# Power.net
KiCad netlist of a schematic drawn in Altium Designer
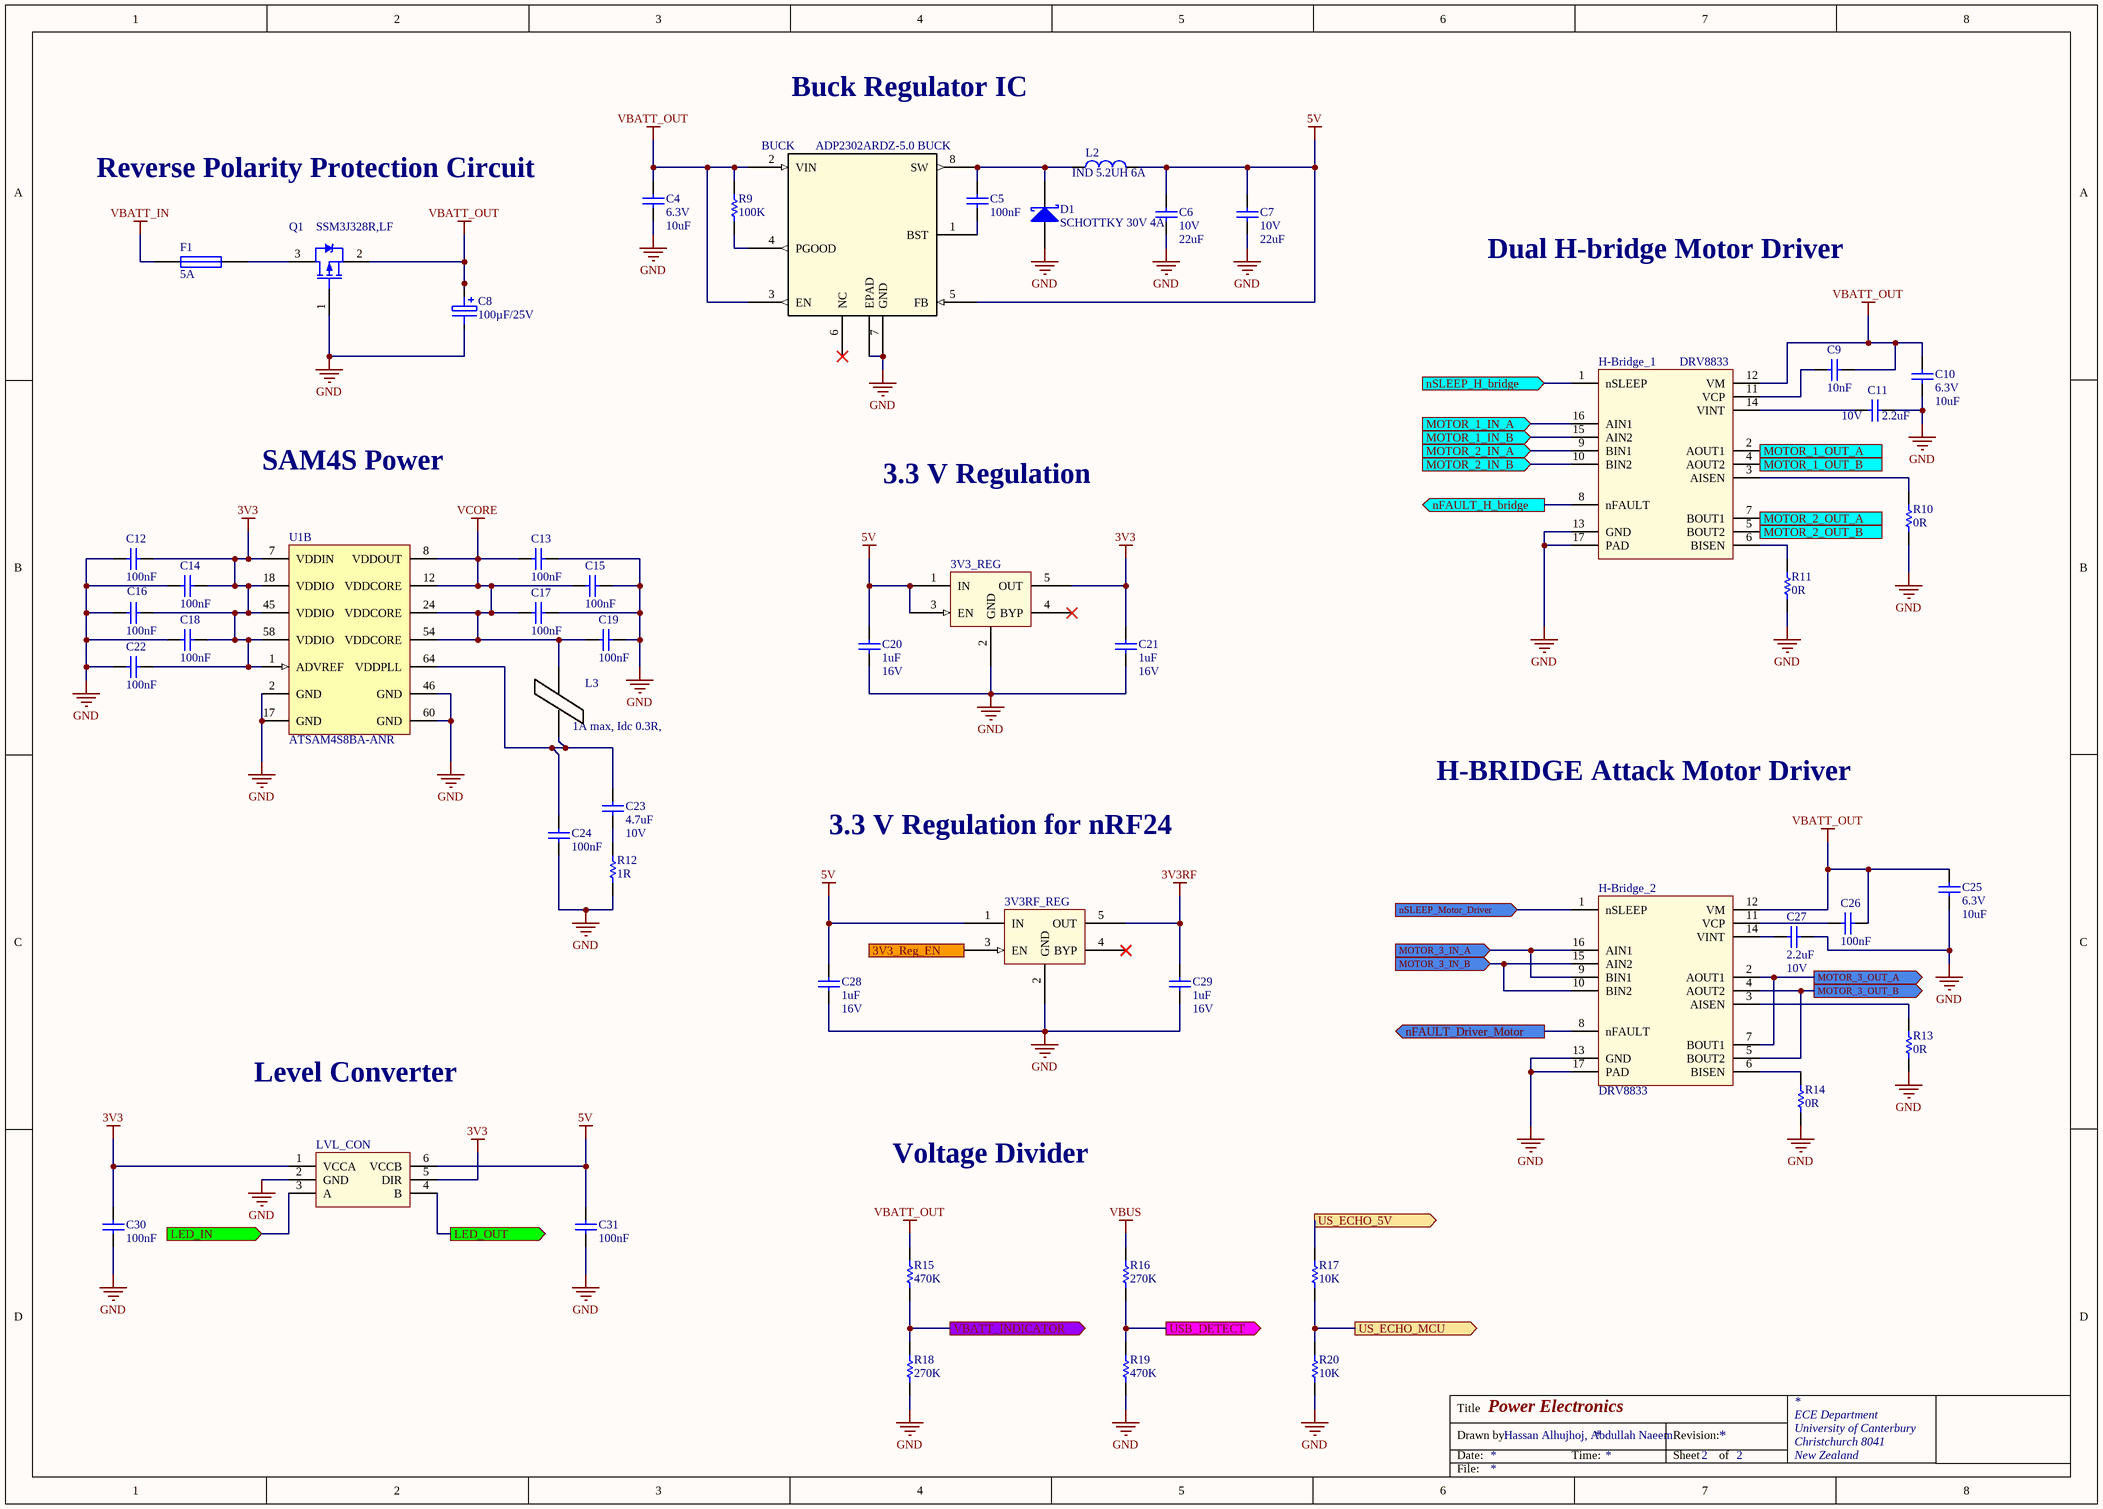
[diagram p0: Power.SchDoc]

(export (version "E")
  (design (tool "Eeschema 10.0.6"))
  (components
    (comp (ref "3V3RF_REG")
      (value "CAT6219-330TDGT3")
      (footprint "SOT95P280X145-5N")
      (description "IC REG LIN 3.3V 500MA TSOT23-5")
      (fields (field (name "BASE PART NUMBER") "CAT6219"))
      (libsource (lib "ENCE461AD19_19V2") (part "SV_CAT6219-330TDGT3"))
    )
    (comp (ref "3V3_REG")
      (value "CAT6219-330TDGT3")
      (footprint "SOT95P280X145-5N")
      (description "IC REG LIN 3.3V 500MA TSOT23-5")
      (fields (field (name "BASE PART NUMBER") "CAT6219"))
      (libsource (lib "ENCE461AD19_19V2") (part "SV_CAT6219-330TDGT3"))
    )
    (comp (ref "BUCK")
      (value "ADP2302ARDZ-5.0 BUCK")
      (footprint "RD_8_1")
      (description "IC REG BUCK 5V 2A 8SOIC")
      (fields (field (name "MANUFACTURER_PART_NUMBER") "ADP2302ARDZ-5.0-R7"))
      (libsource (lib "ENCE461AD19_19V2") (part "ADP2302ARDZ-5.0-R7"))
    )
    (comp (ref "C4")
      (value "10uF")
      (footprint "CAPC1608L")
      (description "CAP CER 10UF X5R +-20% 6V3 0603")
      (fields (field (name "VOLTAGE - RATED") "6.3V"))
      (libsource (lib "ECE AD19Components_19V1") (part "CC_10uF_0603"))
    )
    (comp (ref "C5")
      (value "100nF")
      (footprint "CAPC1608L")
      (description "CAP CER 100nF X7R +-10% 50V 0603")
      (libsource (lib "ECE AD19Components_19V1") (part "CC_100nF_0603"))
    )
    (comp (ref "C6")
      (value "22uF")
      (footprint "CAPC3216L")
      (description "CAP CER 22uF Y5V -20% +80% 10V 1206")
      (fields (field (name "MAX VOLTAGE") "10V"))
      (libsource (lib "ECE AD19Components_19V1") (part "CC_22uF_1206"))
    )
    (comp (ref "C7")
      (value "22uF")
      (footprint "CAPC3216L")
      (description "CAP CER 22uF Y5V -20% +80% 10V 1206")
      (fields (field (name "MAX VOLTAGE") "10V"))
      (libsource (lib "ECE AD19Components_19V1") (part "CC_22uF_1206"))
    )
    (comp (ref "C8")
      (value "100µF/25V")
      (footprint "CAPAE6666X77M")
      (description "CAP ALUM 100UF 25V 20% SMD")
      (fields
        (field (name "MANUFACTURER") "Nichicon")
        (field (name "MANUFACTURER PART NUMBER") "UWT1E101MCL1GS")
        (field (name "CAPACITANCE") "100µF/25V")
      )
      (libsource (lib "ECE AD19Components_19V1") (part "CA_100uF_25V"))
    )
    (comp (ref "C9")
      (value "10nF")
      (footprint "CAPC1608L")
      (description "CAP CER 10nF X7R +-10% 50V 0603")
      (libsource (lib "ECE AD19Components_19V1") (part "CC_10nF_0603"))
    )
    (comp (ref "C10")
      (value "10uF")
      (footprint "CAPC1608L")
      (description "CAP CER 10UF X5R +-20% 6V3 0603")
      (fields (field (name "VOLTAGE - RATED") "6.3V"))
      (libsource (lib "ECE AD19Components_19V1") (part "CC_10uF_0603"))
    )
    (comp (ref "C11")
      (value "2.2uF")
      (footprint "CAPC1608L")
      (description "CAP CER 2.2uF X5R +-20% 10V 0603")
      (fields (field (name "MAX VOLTAGE") "10V"))
      (libsource (lib "ECE AD19Components_19V1") (part "CC_2.2uF_0603"))
    )
    (comp (ref "C12")
      (value "100nF")
      (footprint "CAPC1608L")
      (description "CAP CER 100nF X7R +-10% 50V 0603")
      (libsource (lib "ECE AD19Components_19V1") (part "CC_100nF_0603"))
    )
    (comp (ref "C13")
      (value "100nF")
      (footprint "CAPC1608L")
      (description "CAP CER 100nF X7R +-10% 50V 0603")
      (libsource (lib "ECE AD19Components_19V1") (part "CC_100nF_0603"))
    )
    (comp (ref "C14")
      (value "100nF")
      (footprint "CAPC1608L")
      (description "CAP CER 100nF X7R +-10% 50V 0603")
      (libsource (lib "ECE AD19Components_19V1") (part "CC_100nF_0603"))
    )
    (comp (ref "C15")
      (value "100nF")
      (footprint "CAPC1608L")
      (description "CAP CER 100nF X7R +-10% 50V 0603")
      (libsource (lib "ECE AD19Components_19V1") (part "CC_100nF_0603"))
    )
    (comp (ref "C16")
      (value "100nF")
      (footprint "CAPC1608L")
      (description "CAP CER 100nF X7R +-10% 50V 0603")
      (libsource (lib "ECE AD19Components_19V1") (part "CC_100nF_0603"))
    )
    (comp (ref "C17")
      (value "100nF")
      (footprint "CAPC1608L")
      (description "CAP CER 100nF X7R +-10% 50V 0603")
      (libsource (lib "ECE AD19Components_19V1") (part "CC_100nF_0603"))
    )
    (comp (ref "C18")
      (value "100nF")
      (footprint "CAPC1608L")
      (description "CAP CER 100nF X7R +-10% 50V 0603")
      (libsource (lib "ECE AD19Components_19V1") (part "CC_100nF_0603"))
    )
    (comp (ref "C19")
      (value "100nF")
      (footprint "CAPC1608L")
      (description "CAP CER 100nF X7R +-10% 50V 0603")
      (libsource (lib "ECE AD19Components_19V1") (part "CC_100nF_0603"))
    )
    (comp (ref "C20")
      (value "1uF")
      (footprint "CAPC1608L")
      (description "CAP CER 1uF Y5V -20% +80% 16V 0603")
      (fields (field (name "MAX VOLTAGE") "16V"))
      (libsource (lib "ECE AD19Components_19V1") (part "CC_1uF_0603"))
    )
    (comp (ref "C21")
      (value "1uF")
      (footprint "CAPC1608L")
      (description "CAP CER 1uF Y5V -20% +80% 16V 0603")
      (fields (field (name "MAX VOLTAGE") "16V"))
      (libsource (lib "ECE AD19Components_19V1") (part "CC_1uF_0603"))
    )
    (comp (ref "C22")
      (value "100nF")
      (footprint "CAPC1608L")
      (description "CAP CER 100nF X7R +-10% 50V 0603")
      (libsource (lib "ECE AD19Components_19V1") (part "CC_100nF_0603"))
    )
    (comp (ref "C23")
      (value "4.7uF")
      (footprint "CAPC1608N")
      (description "CAP CER 4.7uF X5R +-20%  10V 0603")
      (fields (field (name "MAX VOLTAGE") "10V"))
      (libsource (lib "ECE AD19Components_19V1") (part "CC_4.7uF_0603"))
    )
    (comp (ref "C24")
      (value "100nF")
      (footprint "CAPC1608L")
      (description "CAP CER 100nF X7R +-10% 50V 0603")
      (libsource (lib "ECE AD19Components_19V1") (part "CC_100nF_0603"))
    )
    (comp (ref "C25")
      (value "10uF")
      (footprint "CAPC1608L")
      (description "CAP CER 10UF X5R +-20% 6V3 0603")
      (fields (field (name "VOLTAGE - RATED") "6.3V"))
      (libsource (lib "ECE AD19Components_19V1") (part "CC_10uF_0603"))
    )
    (comp (ref "C26")
      (value "100nF")
      (footprint "CAPC1608L")
      (description "CAP CER 100nF X7R +-10% 50V 0603")
      (libsource (lib "ECE AD19Components_19V1") (part "CC_100nF_0603"))
    )
    (comp (ref "C27")
      (value "2.2uF")
      (footprint "CAPC1608L")
      (description "CAP CER 2.2uF X5R +-20% 10V 0603")
      (fields (field (name "MAX VOLTAGE") "10V"))
      (libsource (lib "ECE AD19Components_19V1") (part "CC_2.2uF_0603"))
    )
    (comp (ref "C28")
      (value "1uF")
      (footprint "CAPC1608L")
      (description "CAP CER 1uF Y5V -20% +80% 16V 0603")
      (fields (field (name "MAX VOLTAGE") "16V"))
      (libsource (lib "ECE AD19Components_19V1") (part "CC_1uF_0603"))
    )
    (comp (ref "C29")
      (value "1uF")
      (footprint "CAPC1608L")
      (description "CAP CER 1uF Y5V -20% +80% 16V 0603")
      (fields (field (name "MAX VOLTAGE") "16V"))
      (libsource (lib "ECE AD19Components_19V1") (part "CC_1uF_0603"))
    )
    (comp (ref "C30")
      (value "100nF")
      (footprint "CAPC1608L")
      (description "CAP CER 100nF X7R +-10% 50V 0603")
      (libsource (lib "ECE AD19Components_19V1") (part "CC_100nF_0603"))
    )
    (comp (ref "C31")
      (value "100nF")
      (footprint "CAPC1608L")
      (description "CAP CER 100nF X7R +-10% 50V 0603")
      (libsource (lib "ECE AD19Components_19V1") (part "CC_100nF_0603"))
    )
    (comp (ref "D1")
      (value "SCHOTTKY 30V 4A")
      (footprint "SMC")
      (description "DIODE SCHOTTKY 30V 4A SMC")
      (fields
        (field (name "MANUFACTURER") "ON Semiconductor")
        (field (name "MANUFACTURER PART NUMBER") "MBRS330T3G")
      )
      (libsource (lib "ENCE461AD19_19V2") (part "MBRS330T3G"))
    )
    (comp (ref "F1")
      (value "5A")
      (footprint "RESC3216N")
      (description "Fuse 5.0A Fast Acting 1206 SMD")
      (fields (field (name "MANUFACTURER PART NUMBER") "C1F5") (field (name "MANUFACTURER") "Bel TRP"))
      (libsource (lib "ECE AD19Components_19V1") (part "FS_Fuse_5.0A"))
    )
    (comp (ref "H-Bridge_1")
      (value "DRV8833")
      (footprint "HTSOP16")
      (description "Dual H-Bridge Motor Driver 1.5A")
      (libsource (lib "ENCE461AD19_19V2") (part "DRV8833"))
    )
    (comp (ref "H-Bridge_2")
      (value "DRV8833")
      (footprint "HTSOP16")
      (description "Dual H-Bridge Motor Driver 1.5A")
      (libsource (lib "ENCE461AD19_19V2") (part "DRV8833"))
    )
    (comp (ref "L2")
      (value "IND 5.2UH 6A")
      (footprint "INDUCTOR5u2")
      (description "FIXED IND 5.2UH 6A 22 MOHM SMD")
      (fields
        (field (name "MANUFACTURER") "Sumida America Components Inc.")
        (field (name "MANUFACTURER PART NUMBER") "CDRH104RNP-5R2NC")
      )
      (libsource (lib "ENCE461AD19_19V2") (part "CDRH104RNP-5R2NC"))
    )
    (comp (ref "L3")
      (value "1A max, Idc 0.3R,")
      (footprint "INDC3216L")
      (description "Ferrite Bead, Rdc 0.3R, Z100MHZ 600R, Imax 1A, SMD 1206")
      (fields
        (field (name "MANUFACTURER") "FAIR-RITE")
        (field (name "MANUFACTURER PART NUMBER") "2512066017Y1")
      )
      (libsource (lib "ECE AD19Components_19V1") (part "IN_Ferrite-Bead"))
    )
    (comp (ref "LVL_CON")
      (value "SN74LVC1T45")
      (footprint "SOT23-6_N")
      (description "1.8V - 5V level converter")
      (libsource (lib "ENCE461_extras_2020") (part "SN74LVC1T45"))
    )
    (comp (ref "Q1")
      (value "SSM3J328R,LF")
      (footprint "SOT23_L")
      (description "MOSFET P-CH 20V 6A SOT23-3")
      (fields
        (field (name "MANUFACTURER") "Toshiba")
        (field (name "MANUFACTURER PART NUMBER") "SSM3J328R,LF")
      )
      (libsource (lib "ECE AD19Components_19V1") (part "TM_SSM3J328R"))
    )
    (comp (ref "R9")
      (value "100K")
      (footprint "RESC1608L")
      (description "RES 100K OHM 1/10W 5% 0603 SMD")
      (libsource (lib "ECE AD19Components_19V1") (part "RS_100K"))
    )
    (comp (ref "R10")
      (value "0R")
      (footprint "RESC1608L")
      (description "RES 0.0 OHM 1/10W 5% 0603 SMD")
      (libsource (lib "ECE AD19Components_19V1") (part "RS_0R0"))
    )
    (comp (ref "R11")
      (value "0R")
      (footprint "RESC1608L")
      (description "RES 0.0 OHM 1/10W 5% 0603 SMD")
      (libsource (lib "ECE AD19Components_19V1") (part "RS_0R0"))
    )
    (comp (ref "R12")
      (value "1R")
      (footprint "RESC3216L")
      (description "RES 1R OHM 1/4W 5% 1206 SMD")
      (libsource (lib "ECE AD19Components_19V1") (part "RT_1R"))
    )
    (comp (ref "R13")
      (value "0R")
      (footprint "RESC1608L")
      (description "RES 0.0 OHM 1/10W 5% 0603 SMD")
      (libsource (lib "ECE AD19Components_19V1") (part "RS_0R0"))
    )
    (comp (ref "R14")
      (value "0R")
      (footprint "RESC1608L")
      (description "RES 0.0 OHM 1/10W 5% 0603 SMD")
      (libsource (lib "ECE AD19Components_19V1") (part "RS_0R0"))
    )
    (comp (ref "R15")
      (value "470K")
      (footprint "RESC1608L")
      (description "RES 27 OHM 1/10W 5% 0603 SMD")
      (libsource (lib "ECE AD19Components_19V1") (part "RS_27R"))
    )
    (comp (ref "R16")
      (value "270K")
      (footprint "RESC1608L")
      (description "RES 27 OHM 1/10W 5% 0603 SMD")
      (libsource (lib "ECE AD19Components_19V1") (part "RS_27R"))
    )
    (comp (ref "R17")
      (value "10K")
      (footprint "RESC1608L")
      (description "RES 10.0K OHM 1/10W 5% 0603 SMD")
      (libsource (lib "ECE AD19Components_19V1") (part "RS_10K"))
    )
    (comp (ref "R18")
      (value "270K")
      (footprint "RESC1608L")
      (description "RES 47 OHM 1/10W 5% 0603 SMD")
      (libsource (lib "ECE AD19Components_19V1") (part "RS_47R"))
    )
    (comp (ref "R19")
      (value "470K")
      (footprint "RESC1608L")
      (description "RES 47 OHM 1/10W 5% 0603 SMD")
      (libsource (lib "ECE AD19Components_19V1") (part "RS_47R"))
    )
    (comp (ref "R20")
      (value "10K")
      (footprint "RESC1608L")
      (description "RES 10.0K OHM 1/10W 5% 0603 SMD")
      (libsource (lib "ECE AD19Components_19V1") (part "RS_10K"))
    )
    (comp (ref "U1")
      (value "ATSAM4S8BA-ANR")
      (footprint "LQFP64_L")
      (description "IC MCU 32BIT 512KB FLASH 64LQFP")
      (fields (field (name "MANUFACTURER") "Atmel"))
      (libsource (lib "ECE AD19Components_19V1") (part "SE_ATSAM4S16BA-MU"))
    )
  )
  (nets
    (net (code "1") (name "/3V3_Reg_EN") (class "Default")
      (node (ref "3V3RF_REG") (pin "3") (pinfunction "EN_3") (pintype "input"))
    )
    (net (code "2") (name "/LED_IN") (class "Default")
      (node (ref "LVL_CON") (pin "3") (pinfunction "A_3") (pintype "passive"))
    )
    (net (code "3") (name "/LED_OUT") (class "Default")
      (node (ref "LVL_CON") (pin "4") (pinfunction "B_4") (pintype "passive"))
    )
    (net (code "4") (name "/MOTOR_1_IN_A") (class "Default")
      (node (ref "H-Bridge_1") (pin "16") (pinfunction "AIN1_16") (pintype "passive"))
    )
    (net (code "5") (name "/MOTOR_1_IN_B") (class "Default")
      (node (ref "H-Bridge_1") (pin "15") (pinfunction "AIN2_15") (pintype "passive"))
    )
    (net (code "6") (name "/MOTOR_1_OUT_A") (class "Default")
      (node (ref "H-Bridge_1") (pin "2") (pinfunction "AOUT1_2") (pintype "passive"))
    )
    (net (code "7") (name "/MOTOR_1_OUT_B") (class "Default")
      (node (ref "H-Bridge_1") (pin "4") (pinfunction "AOUT2_4") (pintype "passive"))
    )
    (net (code "8") (name "/MOTOR_2_IN_A") (class "Default")
      (node (ref "H-Bridge_1") (pin "9") (pinfunction "BIN1_9") (pintype "passive"))
    )
    (net (code "9") (name "/MOTOR_2_IN_B") (class "Default")
      (node (ref "H-Bridge_1") (pin "10") (pinfunction "BIN2_10") (pintype "passive"))
    )
    (net (code "10") (name "/MOTOR_2_OUT_A") (class "Default")
      (node (ref "H-Bridge_1") (pin "7") (pinfunction "BOUT1_7") (pintype "passive"))
    )
    (net (code "11") (name "/MOTOR_2_OUT_B") (class "Default")
      (node (ref "H-Bridge_1") (pin "5") (pinfunction "BOUT2_5") (pintype "passive"))
    )
    (net (code "12") (name "/MOTOR_3_IN_A") (class "Default")
      (node (ref "H-Bridge_2") (pin "16") (pinfunction "AIN1_16") (pintype "passive"))
      (node (ref "H-Bridge_2") (pin "9") (pinfunction "BIN1_9") (pintype "passive"))
    )
    (net (code "13") (name "/MOTOR_3_IN_B") (class "Default")
      (node (ref "H-Bridge_2") (pin "10") (pinfunction "BIN2_10") (pintype "passive"))
      (node (ref "H-Bridge_2") (pin "15") (pinfunction "AIN2_15") (pintype "passive"))
    )
    (net (code "14") (name "/MOTOR_3_OUT_A") (class "Default")
      (node (ref "H-Bridge_2") (pin "2") (pinfunction "AOUT1_2") (pintype "passive"))
      (node (ref "H-Bridge_2") (pin "7") (pinfunction "BOUT1_7") (pintype "passive"))
    )
    (net (code "15") (name "/MOTOR_3_OUT_B") (class "Default")
      (node (ref "H-Bridge_2") (pin "4") (pinfunction "AOUT2_4") (pintype "passive"))
      (node (ref "H-Bridge_2") (pin "5") (pinfunction "BOUT2_5") (pintype "passive"))
    )
    (net (code "16") (name "/USB_DETECT") (class "Default")
      (node (ref "R16") (pin "1") (pinfunction "1_1") (pintype "passive"))
      (node (ref "R19") (pin "2") (pinfunction "2_2") (pintype "passive"))
    )
    (net (code "17") (name "/US_ECHO_5V") (class "Default")
      (node (ref "R17") (pin "2") (pinfunction "2_2") (pintype "passive"))
    )
    (net (code "18") (name "/US_ECHO_MCU") (class "Default")
      (node (ref "R17") (pin "1") (pinfunction "1_1") (pintype "passive"))
      (node (ref "R20") (pin "2") (pinfunction "2_2") (pintype "passive"))
    )
    (net (code "19") (name "/VBATT_INDICATOR") (class "Default")
      (node (ref "R15") (pin "1") (pinfunction "1_1") (pintype "passive"))
      (node (ref "R18") (pin "2") (pinfunction "2_2") (pintype "passive"))
    )
    (net (code "20") (name "/nFAULT_Driver_Motor") (class "Default")
      (node (ref "H-Bridge_2") (pin "8") (pinfunction "nFAULT_8") (pintype "passive"))
    )
    (net (code "21") (name "/nFAULT_H_bridge") (class "Default")
      (node (ref "H-Bridge_1") (pin "8") (pinfunction "nFAULT_8") (pintype "passive"))
    )
    (net (code "22") (name "/nSLEEP_H_bridge") (class "Default")
      (node (ref "H-Bridge_1") (pin "1") (pinfunction "nSLEEP_1") (pintype "passive"))
    )
    (net (code "23") (name "/nSLEEP_Motor_Driver") (class "Default")
      (node (ref "H-Bridge_2") (pin "1") (pinfunction "nSLEEP_1") (pintype "passive"))
    )
    (net (code "24") (name "3V3") (class "Default")
      (node (ref "3V3_REG") (pin "5") (pinfunction "OUT_5") (pintype "power_in"))
      (node (ref "C12") (pin "2") (pinfunction "2_2") (pintype "passive"))
      (node (ref "C14") (pin "2") (pinfunction "2_2") (pintype "passive"))
      (node (ref "C16") (pin "2") (pinfunction "2_2") (pintype "passive"))
      (node (ref "C18") (pin "2") (pinfunction "2_2") (pintype "passive"))
      (node (ref "C21") (pin "2") (pinfunction "2_2") (pintype "passive"))
      (node (ref "C22") (pin "2") (pinfunction "2_2") (pintype "passive"))
      (node (ref "C30") (pin "2") (pinfunction "2_2") (pintype "passive"))
      (node (ref "LVL_CON") (pin "1") (pinfunction "VCCA_1") (pintype "passive"))
      (node (ref "LVL_CON") (pin "5") (pinfunction "DIR_5") (pintype "passive"))
      (node (ref "U1") (pin "1") (pinfunction "ADVREF_1") (pintype "input"))
      (node (ref "U1") (pin "18") (pinfunction "VDDIO_18") (pintype "power_in"))
      (node (ref "U1") (pin "45") (pinfunction "VDDIO_45") (pintype "power_in"))
      (node (ref "U1") (pin "58") (pinfunction "VDDIO_58") (pintype "power_in"))
      (node (ref "U1") (pin "7") (pinfunction "VDDIN_7") (pintype "power_in"))
    )
    (net (code "25") (name "3V3RF") (class "Default")
      (node (ref "3V3RF_REG") (pin "5") (pinfunction "OUT_5") (pintype "power_in"))
      (node (ref "C29") (pin "2") (pinfunction "2_2") (pintype "passive"))
    )
    (net (code "26") (name "5V") (class "Default")
      (node (ref "3V3RF_REG") (pin "1") (pinfunction "IN_1") (pintype "power_in"))
      (node (ref "3V3_REG") (pin "1") (pinfunction "IN_1") (pintype "power_in"))
      (node (ref "3V3_REG") (pin "3") (pinfunction "EN_3") (pintype "input"))
      (node (ref "BUCK") (pin "5") (pinfunction "FB_5") (pintype "input"))
      (node (ref "C20") (pin "1") (pinfunction "1_1") (pintype "passive"))
      (node (ref "C28") (pin "1") (pinfunction "1_1") (pintype "passive"))
      (node (ref "C31") (pin "2") (pinfunction "2_2") (pintype "passive"))
      (node (ref "C6") (pin "2") (pinfunction "2_2") (pintype "passive"))
      (node (ref "C7") (pin "2") (pinfunction "2_2") (pintype "passive"))
      (node (ref "L2") (pin "2") (pintype "passive"))
      (node (ref "LVL_CON") (pin "6") (pinfunction "VCCB_6") (pintype "passive"))
    )
    (net (code "27") (name "GND") (class "Default")
      (node (ref "3V3RF_REG") (pin "2") (pinfunction "GND_2") (pintype "power_in"))
      (node (ref "3V3_REG") (pin "2") (pinfunction "GND_2") (pintype "power_in"))
      (node (ref "BUCK") (pin "7") (pinfunction "GND_7") (pintype "power_in"))
      (node (ref "BUCK") (pin "EPAD") (pinfunction "EPAD_EPAD") (pintype "passive"))
      (node (ref "C10") (pin "1") (pinfunction "1_1") (pintype "passive"))
      (node (ref "C11") (pin "2") (pinfunction "2_2") (pintype "passive"))
      (node (ref "C12") (pin "1") (pinfunction "1_1") (pintype "passive"))
      (node (ref "C13") (pin "2") (pinfunction "2_2") (pintype "passive"))
      (node (ref "C14") (pin "1") (pinfunction "1_1") (pintype "passive"))
      (node (ref "C15") (pin "2") (pinfunction "2_2") (pintype "passive"))
      (node (ref "C16") (pin "1") (pinfunction "1_1") (pintype "passive"))
      (node (ref "C17") (pin "2") (pinfunction "2_2") (pintype "passive"))
      (node (ref "C18") (pin "1") (pinfunction "1_1") (pintype "passive"))
      (node (ref "C19") (pin "2") (pinfunction "2_2") (pintype "passive"))
      (node (ref "C20") (pin "2") (pinfunction "2_2") (pintype "passive"))
      (node (ref "C21") (pin "1") (pinfunction "1_1") (pintype "passive"))
      (node (ref "C22") (pin "1") (pinfunction "1_1") (pintype "passive"))
      (node (ref "C24") (pin "1") (pinfunction "1_1") (pintype "passive"))
      (node (ref "C25") (pin "1") (pinfunction "1_1") (pintype "passive"))
      (node (ref "C27") (pin "2") (pinfunction "2_2") (pintype "passive"))
      (node (ref "C28") (pin "2") (pinfunction "2_2") (pintype "passive"))
      (node (ref "C29") (pin "1") (pinfunction "1_1") (pintype "passive"))
      (node (ref "C30") (pin "1") (pinfunction "1_1") (pintype "passive"))
      (node (ref "C31") (pin "1") (pinfunction "1_1") (pintype "passive"))
      (node (ref "C4") (pin "1") (pinfunction "1_1") (pintype "passive"))
      (node (ref "C6") (pin "1") (pinfunction "1_1") (pintype "passive"))
      (node (ref "C7") (pin "1") (pinfunction "1_1") (pintype "passive"))
      (node (ref "C8") (pin "1") (pintype "passive"))
      (node (ref "D1") (pin "1") (pinfunction "A_1") (pintype "passive"))
      (node (ref "H-Bridge_1") (pin "13") (pinfunction "GND_13") (pintype "passive"))
      (node (ref "H-Bridge_1") (pin "17") (pinfunction "PAD_17") (pintype "passive"))
      (node (ref "H-Bridge_2") (pin "13") (pinfunction "GND_13") (pintype "passive"))
      (node (ref "H-Bridge_2") (pin "17") (pinfunction "PAD_17") (pintype "passive"))
      (node (ref "LVL_CON") (pin "2") (pinfunction "GND_2") (pintype "passive"))
      (node (ref "Q1") (pin "1") (pinfunction "1_1") (pintype "passive"))
      (node (ref "R10") (pin "2") (pinfunction "2_2") (pintype "passive"))
      (node (ref "R11") (pin "1") (pinfunction "1_1") (pintype "passive"))
      (node (ref "R12") (pin "2") (pinfunction "2_2") (pintype "passive"))
      (node (ref "R13") (pin "2") (pinfunction "2_2") (pintype "passive"))
      (node (ref "R14") (pin "2") (pinfunction "2_2") (pintype "passive"))
      (node (ref "R18") (pin "1") (pinfunction "1_1") (pintype "passive"))
      (node (ref "R19") (pin "1") (pinfunction "1_1") (pintype "passive"))
      (node (ref "R20") (pin "1") (pinfunction "1_1") (pintype "passive"))
      (node (ref "U1") (pin "17") (pinfunction "GND_17") (pintype "power_in"))
      (node (ref "U1") (pin "2") (pinfunction "GND_2") (pintype "power_in"))
      (node (ref "U1") (pin "46") (pinfunction "GND_46") (pintype "power_in"))
      (node (ref "U1") (pin "60") (pinfunction "GND_60") (pintype "power_in"))
    )
    (net (code "28") (name "Net-(BUCK-BST)") (class "Default")
      (node (ref "BUCK") (pin "1") (pinfunction "BST_1") (pintype "passive"))
      (node (ref "C5") (pin "1") (pinfunction "1_1") (pintype "passive"))
    )
    (net (code "29") (name "Net-(BUCK-PGOOD)") (class "Default")
      (node (ref "BUCK") (pin "4") (pinfunction "PGOOD_4") (pintype "output"))
      (node (ref "R9") (pin "1") (pinfunction "1_1") (pintype "passive"))
    )
    (net (code "30") (name "Net-(BUCK-SW)") (class "Default")
      (node (ref "BUCK") (pin "8") (pinfunction "SW_8") (pintype "output"))
      (node (ref "C5") (pin "2") (pinfunction "2_2") (pintype "passive"))
      (node (ref "D1") (pin "2") (pinfunction "K_2") (pintype "passive"))
      (node (ref "L2") (pin "1") (pintype "passive"))
    )
    (net (code "31") (name "Net-(C23-Pad1)") (class "Default")
      (node (ref "C23") (pin "1") (pinfunction "1_1") (pintype "passive"))
      (node (ref "R12") (pin "1") (pinfunction "1_1") (pintype "passive"))
    )
    (net (code "32") (name "Net-(F1-Pad2)") (class "Default")
      (node (ref "F1") (pin "2") (pinfunction "2_2") (pintype "passive"))
      (node (ref "Q1") (pin "3") (pinfunction "3_3") (pintype "passive"))
    )
    (net (code "33") (name "Net-(H-Bridge_1-AISEN)") (class "Default")
      (node (ref "H-Bridge_1") (pin "3") (pinfunction "AISEN_3") (pintype "passive"))
      (node (ref "R10") (pin "1") (pinfunction "1_1") (pintype "passive"))
    )
    (net (code "34") (name "Net-(H-Bridge_1-BISEN)") (class "Default")
      (node (ref "H-Bridge_1") (pin "6") (pinfunction "BISEN_6") (pintype "passive"))
      (node (ref "R11") (pin "2") (pinfunction "2_2") (pintype "passive"))
    )
    (net (code "35") (name "Net-(H-Bridge_1-VCP)") (class "Default")
      (node (ref "C9") (pin "1") (pinfunction "1_1") (pintype "passive"))
      (node (ref "H-Bridge_1") (pin "11") (pinfunction "VCP_11") (pintype "passive"))
    )
    (net (code "36") (name "Net-(H-Bridge_1-VINT)") (class "Default")
      (node (ref "C11") (pin "1") (pinfunction "1_1") (pintype "passive"))
      (node (ref "H-Bridge_1") (pin "14") (pinfunction "VINT_14") (pintype "passive"))
    )
    (net (code "37") (name "Net-(H-Bridge_2-AISEN)") (class "Default")
      (node (ref "H-Bridge_2") (pin "3") (pinfunction "AISEN_3") (pintype "passive"))
      (node (ref "R13") (pin "1") (pinfunction "1_1") (pintype "passive"))
    )
    (net (code "38") (name "Net-(H-Bridge_2-BISEN)") (class "Default")
      (node (ref "H-Bridge_2") (pin "6") (pinfunction "BISEN_6") (pintype "passive"))
      (node (ref "R14") (pin "1") (pinfunction "1_1") (pintype "passive"))
    )
    (net (code "39") (name "Net-(H-Bridge_2-VCP)") (class "Default")
      (node (ref "C26") (pin "1") (pinfunction "1_1") (pintype "passive"))
      (node (ref "H-Bridge_2") (pin "11") (pinfunction "VCP_11") (pintype "passive"))
    )
    (net (code "40") (name "Net-(H-Bridge_2-VINT)") (class "Default")
      (node (ref "C27") (pin "1") (pinfunction "1_1") (pintype "passive"))
      (node (ref "H-Bridge_2") (pin "14") (pinfunction "VINT_14") (pintype "passive"))
    )
    (net (code "41") (name "Net-(U1B-VDDPLL)") (class "Default")
      (node (ref "C23") (pin "2") (pinfunction "2_2") (pintype "passive"))
      (node (ref "C24") (pin "2") (pinfunction "2_2") (pintype "passive"))
      (node (ref "L3") (pin "1") (pinfunction "1_1") (pintype "passive"))
      (node (ref "U1") (pin "64") (pinfunction "VDDPLL_64") (pintype "power_in"))
    )
    (net (code "42") (name "VBATT_IN") (class "Default")
      (node (ref "F1") (pin "1") (pinfunction "1_1") (pintype "passive"))
    )
    (net (code "43") (name "VBATT_OUT") (class "Default")
      (node (ref "BUCK") (pin "2") (pinfunction "VIN_2") (pintype "input"))
      (node (ref "BUCK") (pin "3") (pinfunction "EN_3") (pintype "output"))
      (node (ref "C10") (pin "2") (pinfunction "2_2") (pintype "passive"))
      (node (ref "C25") (pin "2") (pinfunction "2_2") (pintype "passive"))
      (node (ref "C26") (pin "2") (pinfunction "2_2") (pintype "passive"))
      (node (ref "C4") (pin "2") (pinfunction "2_2") (pintype "passive"))
      (node (ref "C8") (pin "2") (pintype "passive"))
      (node (ref "C9") (pin "2") (pinfunction "2_2") (pintype "passive"))
      (node (ref "H-Bridge_1") (pin "12") (pinfunction "VM_12") (pintype "passive"))
      (node (ref "H-Bridge_2") (pin "12") (pinfunction "VM_12") (pintype "passive"))
      (node (ref "Q1") (pin "2") (pinfunction "2_2") (pintype "passive"))
      (node (ref "R15") (pin "2") (pinfunction "2_2") (pintype "passive"))
      (node (ref "R9") (pin "2") (pinfunction "2_2") (pintype "passive"))
    )
    (net (code "44") (name "VBUS") (class "Default")
      (node (ref "R16") (pin "2") (pinfunction "2_2") (pintype "passive"))
    )
    (net (code "45") (name "VCORE") (class "Default")
      (node (ref "C13") (pin "1") (pinfunction "1_1") (pintype "passive"))
      (node (ref "C15") (pin "1") (pinfunction "1_1") (pintype "passive"))
      (node (ref "C17") (pin "1") (pinfunction "1_1") (pintype "passive"))
      (node (ref "C19") (pin "1") (pinfunction "1_1") (pintype "passive"))
      (node (ref "L3") (pin "2") (pinfunction "2_2") (pintype "passive"))
      (node (ref "U1") (pin "12") (pinfunction "VDDCORE_12") (pintype "power_in"))
      (node (ref "U1") (pin "24") (pinfunction "VDDCORE_24") (pintype "power_in"))
      (node (ref "U1") (pin "54") (pinfunction "VDDCORE_54") (pintype "power_in"))
      (node (ref "U1") (pin "8") (pinfunction "VDDOUT_8") (pintype "power_in"))
    )
    (net (code "46") (name "unconnected-(3V3RF_REG-BYP-Pad4)") (class "Default")
      (node (ref "3V3RF_REG") (pin "4") (pinfunction "BYP_4") (pintype "passive+no_connect"))
    )
    (net (code "47") (name "unconnected-(3V3_REG-BYP-Pad4)") (class "Default")
      (node (ref "3V3_REG") (pin "4") (pinfunction "BYP_4") (pintype "passive+no_connect"))
    )
    (net (code "48") (name "unconnected-(BUCK-NC-Pad6)") (class "Default")
      (node (ref "BUCK") (pin "6") (pinfunction "NC_6") (pintype "passive+no_connect"))
    )
  )
)
